# 6coils-1-discrete.net
KiCad netlist of a schematic drawn in EasyEDA
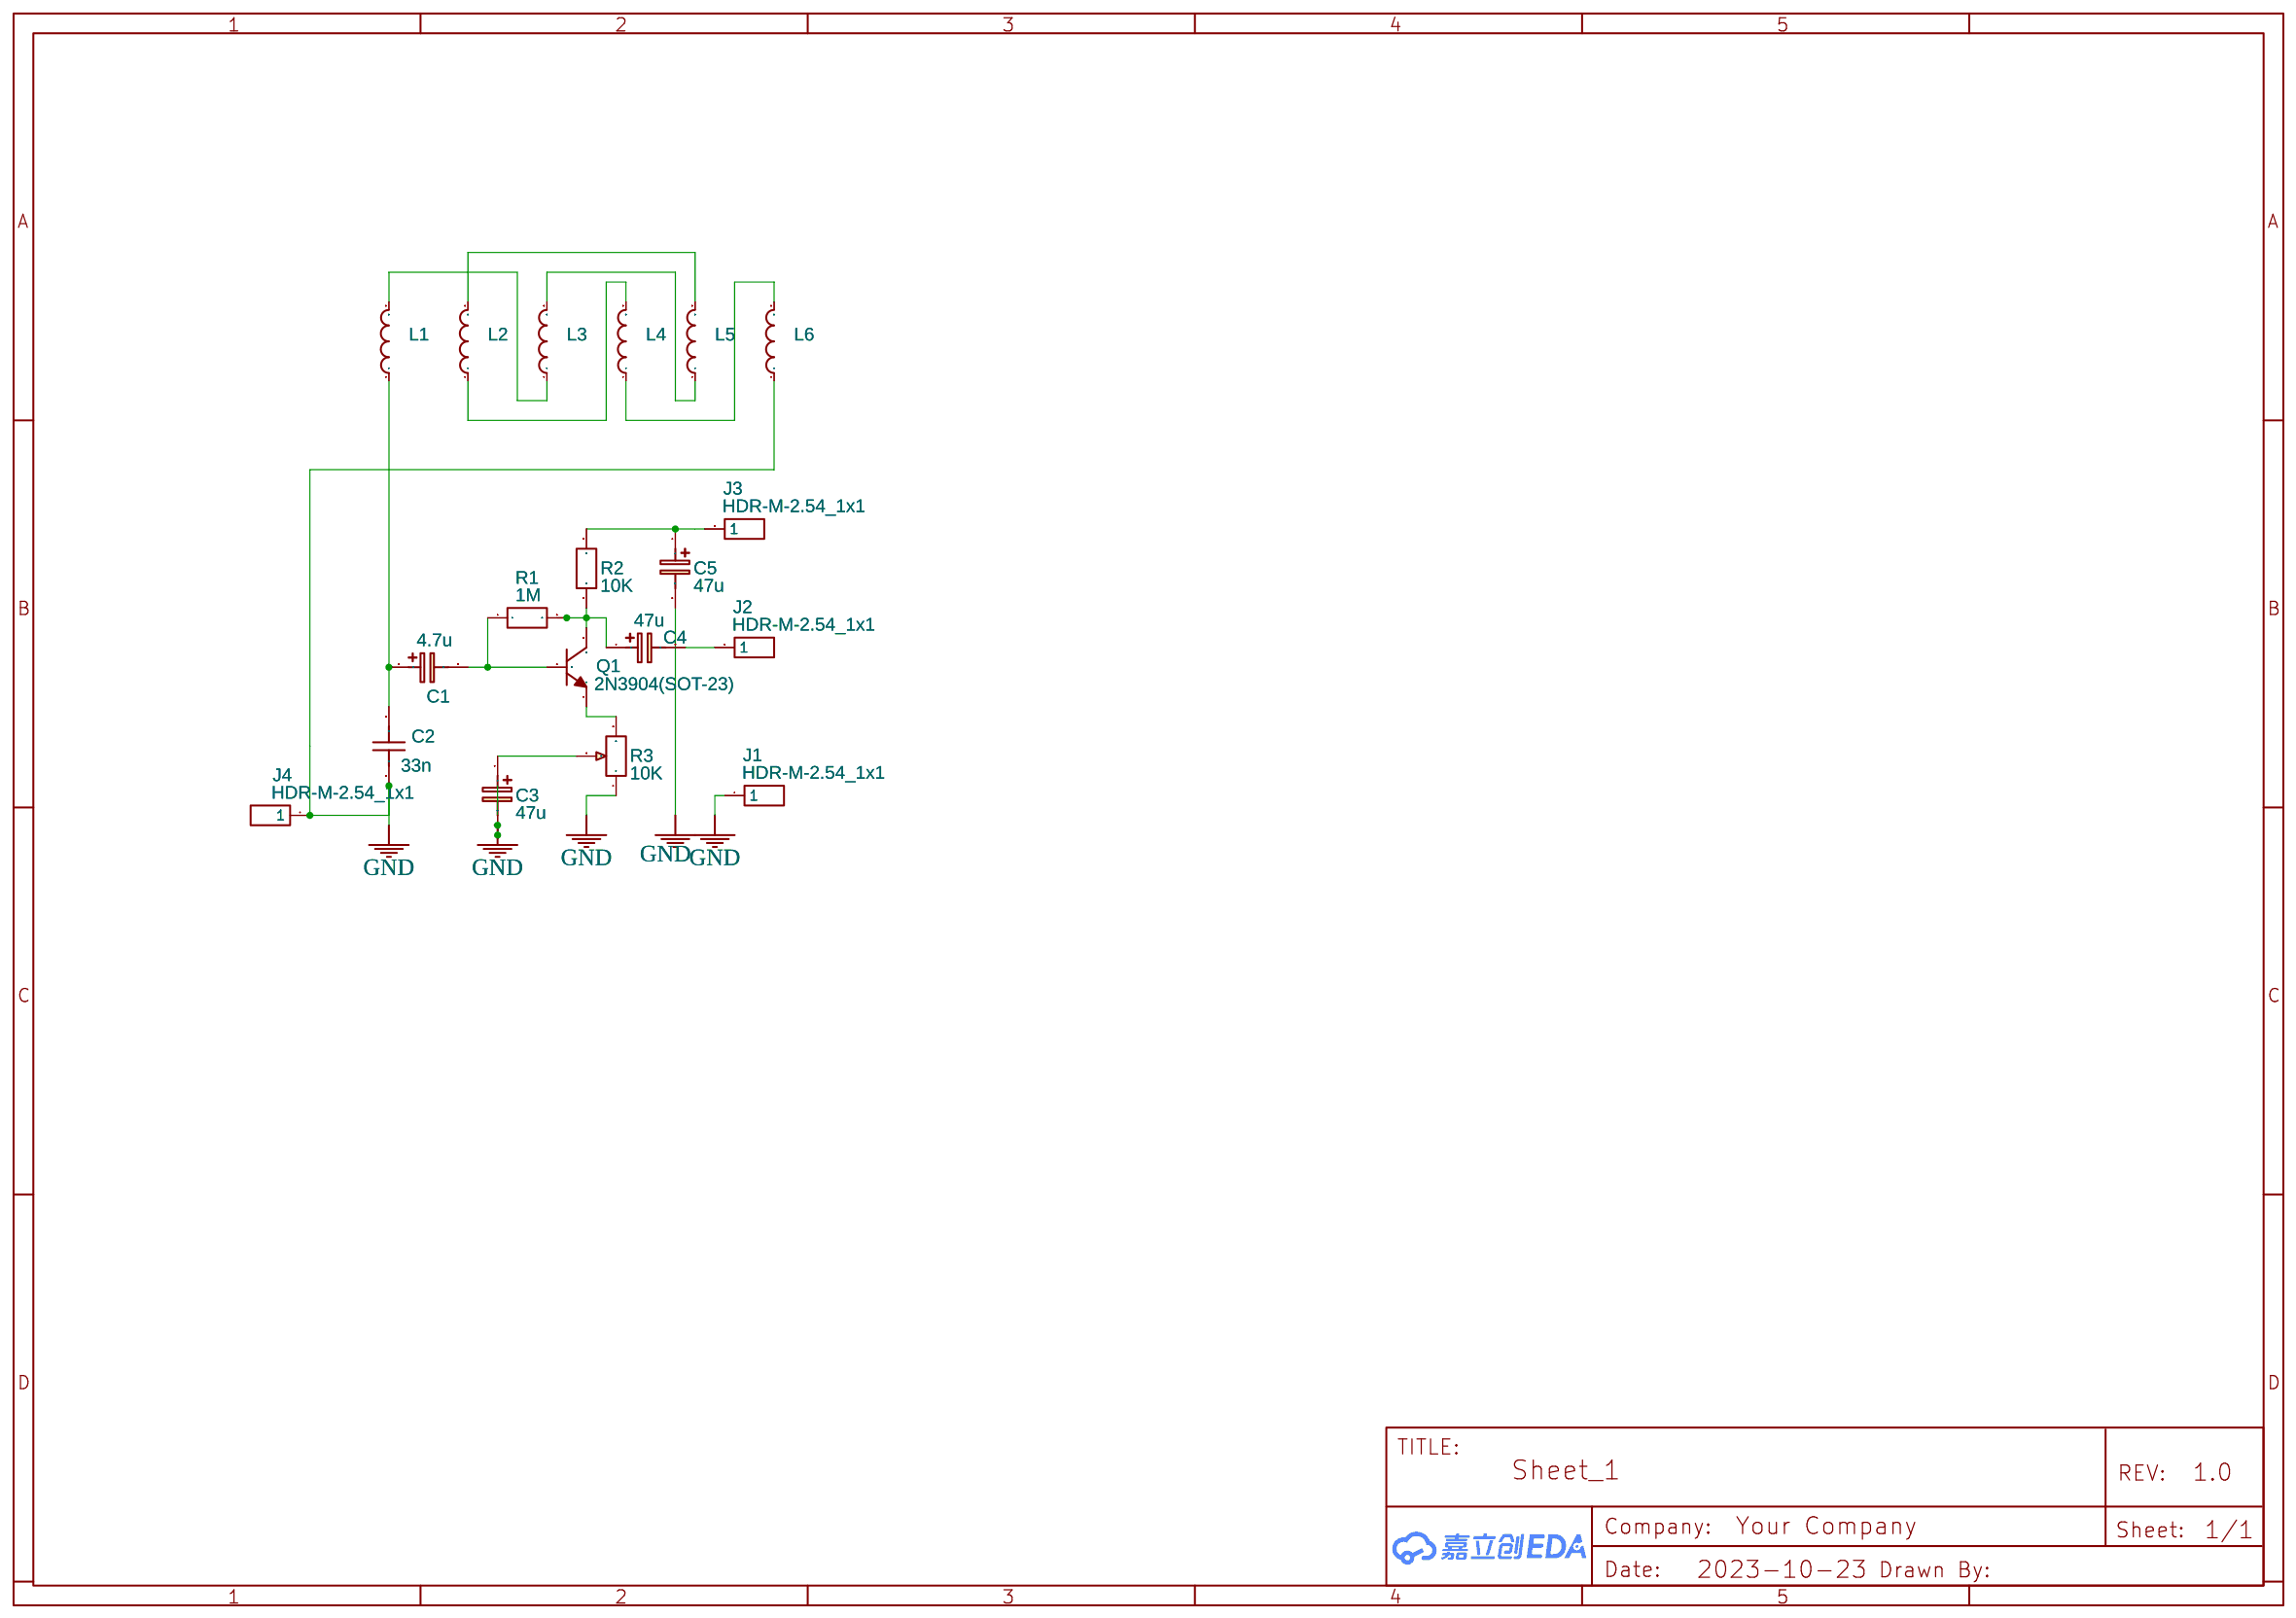
[diagram p0: schematic sheet]

(export (version "E")
  (design (tool "Eeschema 10.0.6"))
  (components
    (comp (ref "C1") (value "4.7u") (libsource (lib "") (part "C_Tan_SMD_A_EU_3")))
    (comp (ref "C2") (value "33n") (libsource (lib "") (part "C_0603_US")))
    (comp (ref "C3") (value "47u") (libsource (lib "") (part "C_Tan_SMD_A_EU_1")))
    (comp (ref "C4") (value "47u") (libsource (lib "") (part "C_Tan_SMD_A_EU")))
    (comp (ref "C5") (value "47u") (libsource (lib "") (part "C_Tan_SMD_A_EU_2")))
    (comp (ref "J1")
      (value "HDR-M-2.54_1x1")
      (fields (field (name "BOM_Supplier Part") "C81276"))
      (libsource (lib "") (part "HDR-M-2.54_1x1"))
    )
    (comp (ref "J2")
      (value "HDR-M-2.54_1x1")
      (fields (field (name "BOM_Supplier Part") "C81276"))
      (libsource (lib "") (part "HDR-M-2.54_1x1"))
    )
    (comp (ref "J3")
      (value "HDR-M-2.54_1x1")
      (fields (field (name "BOM_Supplier Part") "C81276"))
      (libsource (lib "") (part "HDR-M-2.54_1x1"))
    )
    (comp (ref "J4")
      (value "HDR-M-2.54_1x1")
      (fields (field (name "BOM_Supplier Part") "C81276"))
      (libsource (lib "") (part "HDR-M-2.54_1x1_1"))
    )
    (comp (ref "L1")
      (value "INDUCTOR_SMD:L_COILCRAFT_XXL4040")
      (fields (field (name "Manufacturer Part") "Inductor_SMD:L_Coilcraft_XxL4040"))
      (libsource (lib "") (part "INDUCTOR_SMD{colon}L_COILCRAFT_XXL4040"))
    )
    (comp (ref "L2")
      (value "INDUCTOR_SMD:L_COILCRAFT_XXL4040")
      (fields (field (name "Manufacturer Part") "Inductor_SMD:L_Coilcraft_XxL4040"))
      (libsource (lib "") (part "INDUCTOR_SMD{colon}L_COILCRAFT_XXL4040"))
    )
    (comp (ref "L3")
      (value "INDUCTOR_SMD:L_COILCRAFT_XXL4040")
      (fields (field (name "Manufacturer Part") "Inductor_SMD:L_Coilcraft_XxL4040"))
      (libsource (lib "") (part "INDUCTOR_SMD{colon}L_COILCRAFT_XXL4040_1"))
    )
    (comp (ref "L4")
      (value "INDUCTOR_SMD:L_COILCRAFT_XXL4040")
      (fields (field (name "Manufacturer Part") "Inductor_SMD:L_Coilcraft_XxL4040"))
      (libsource (lib "") (part "INDUCTOR_SMD{colon}L_COILCRAFT_XXL4040_1"))
    )
    (comp (ref "L5")
      (value "INDUCTOR_SMD:L_COILCRAFT_XXL4040")
      (fields (field (name "Manufacturer Part") "Inductor_SMD:L_Coilcraft_XxL4040"))
      (libsource (lib "") (part "INDUCTOR_SMD{colon}L_COILCRAFT_XXL4040_1"))
    )
    (comp (ref "L6")
      (value "INDUCTOR_SMD:L_COILCRAFT_XXL4040")
      (fields (field (name "Manufacturer Part") "Inductor_SMD:L_Coilcraft_XxL4040"))
      (libsource (lib "") (part "INDUCTOR_SMD{colon}L_COILCRAFT_XXL4040_1"))
    )
    (comp (ref "Q1")
      (value "2N3904(SOT-23)")
      (fields
        (field (name "BOM_Manufacturer Part") "2n3904S-RTK/PS")
        (field (name "BOM_Supplier Part") "C18536")
      )
      (libsource (lib "") (part "2N3904(SOT-23)"))
    )
    (comp (ref "R1") (value "1M") (libsource (lib "") (part "R_0603_EU_1")))
    (comp (ref "R2") (value "10K") (libsource (lib "") (part "R_0603_EU")))
    (comp (ref "R3")
      (value "10K")
      (fields (field (name "Manufacturer Part") "RM063-103 10K") (field (name "Manufacturer") "JML"))
      (libsource (lib "") (part "RM063-103 10K"))
    )
  )
  (nets
    (net (code "1") (name "GND") (class "Default")
      (node (ref "C2") (pin "1") (pinfunction "1_1") (pintype "unspecified"))
      (node (ref "C3") (pin "2") (pinfunction "2_2") (pintype "unspecified"))
      (node (ref "C5") (pin "2") (pinfunction "2_2") (pintype "unspecified"))
      (node (ref "J1") (pin "1") (pinfunction "1_1") (pintype "input"))
      (node (ref "J4") (pin "1") (pinfunction "1_1") (pintype "input"))
      (node (ref "L6") (pin "1") (pinfunction "1_1") (pintype "unspecified"))
      (node (ref "R3") (pin "1") (pinfunction "1_1") (pintype "input"))
    )
    (net (code "2") (name "Net-(C1-Pad1)") (class "Default")
      (node (ref "C1") (pin "1") (pinfunction "1_1") (pintype "unspecified"))
      (node (ref "C2") (pin "2") (pinfunction "2_2") (pintype "unspecified"))
      (node (ref "L1") (pin "1") (pinfunction "1_1") (pintype "unspecified"))
    )
    (net (code "3") (name "Net-(C3-Pad1)") (class "Default")
      (node (ref "C3") (pin "1") (pinfunction "1_1") (pintype "unspecified"))
      (node (ref "R3") (pin "2") (pinfunction "2_2") (pintype "input"))
    )
    (net (code "4") (name "Net-(C4-Pad2)") (class "Default")
      (node (ref "C4") (pin "2") (pinfunction "2_2") (pintype "unspecified"))
      (node (ref "J2") (pin "1") (pinfunction "1_1") (pintype "input"))
    )
    (net (code "5") (name "Net-(C5-Pad1)") (class "Default")
      (node (ref "C5") (pin "1") (pinfunction "1_1") (pintype "unspecified"))
      (node (ref "J3") (pin "1") (pinfunction "1_1") (pintype "input"))
      (node (ref "R2") (pin "2") (pinfunction "2_2") (pintype "unspecified"))
    )
    (net (code "6") (name "Net-(L1-Pad2)") (class "Default")
      (node (ref "L1") (pin "2") (pinfunction "2_2") (pintype "unspecified"))
      (node (ref "L3") (pin "1") (pinfunction "1_1") (pintype "unspecified"))
    )
    (net (code "7") (name "Net-(L2-Pad1)") (class "Default")
      (node (ref "L2") (pin "1") (pinfunction "1_1") (pintype "unspecified"))
      (node (ref "L4") (pin "2") (pinfunction "2_2") (pintype "unspecified"))
    )
    (net (code "8") (name "Net-(L2-Pad2)") (class "Default")
      (node (ref "L2") (pin "2") (pinfunction "2_2") (pintype "unspecified"))
      (node (ref "L5") (pin "2") (pinfunction "2_2") (pintype "unspecified"))
    )
    (net (code "9") (name "Net-(L3-Pad2)") (class "Default")
      (node (ref "L3") (pin "2") (pinfunction "2_2") (pintype "unspecified"))
      (node (ref "L5") (pin "1") (pinfunction "1_1") (pintype "unspecified"))
    )
    (net (code "10") (name "Net-(L4-Pad1)") (class "Default")
      (node (ref "L4") (pin "1") (pinfunction "1_1") (pintype "unspecified"))
      (node (ref "L6") (pin "2") (pinfunction "2_2") (pintype "unspecified"))
    )
    (net (code "11") (name "Net-(Q1-B)") (class "Default")
      (node (ref "C1") (pin "2") (pinfunction "2_2") (pintype "unspecified"))
      (node (ref "Q1") (pin "2") (pinfunction "B_2") (pintype "input"))
      (node (ref "R1") (pin "1") (pinfunction "1_1") (pintype "unspecified"))
    )
    (net (code "12") (name "Net-(Q1-C)") (class "Default")
      (node (ref "C4") (pin "1") (pinfunction "1_1") (pintype "unspecified"))
      (node (ref "Q1") (pin "3") (pinfunction "C_3") (pintype "input"))
      (node (ref "R1") (pin "2") (pinfunction "2_2") (pintype "unspecified"))
      (node (ref "R2") (pin "1") (pinfunction "1_1") (pintype "unspecified"))
    )
    (net (code "13") (name "Net-(Q1-E)") (class "Default")
      (node (ref "Q1") (pin "1") (pinfunction "E_1") (pintype "input"))
      (node (ref "R3") (pin "3") (pinfunction "3_3") (pintype "input"))
    )
  )
)
